# mixer_board_smd_full.net
KiCad netlist of a schematic drawn in EAGLE
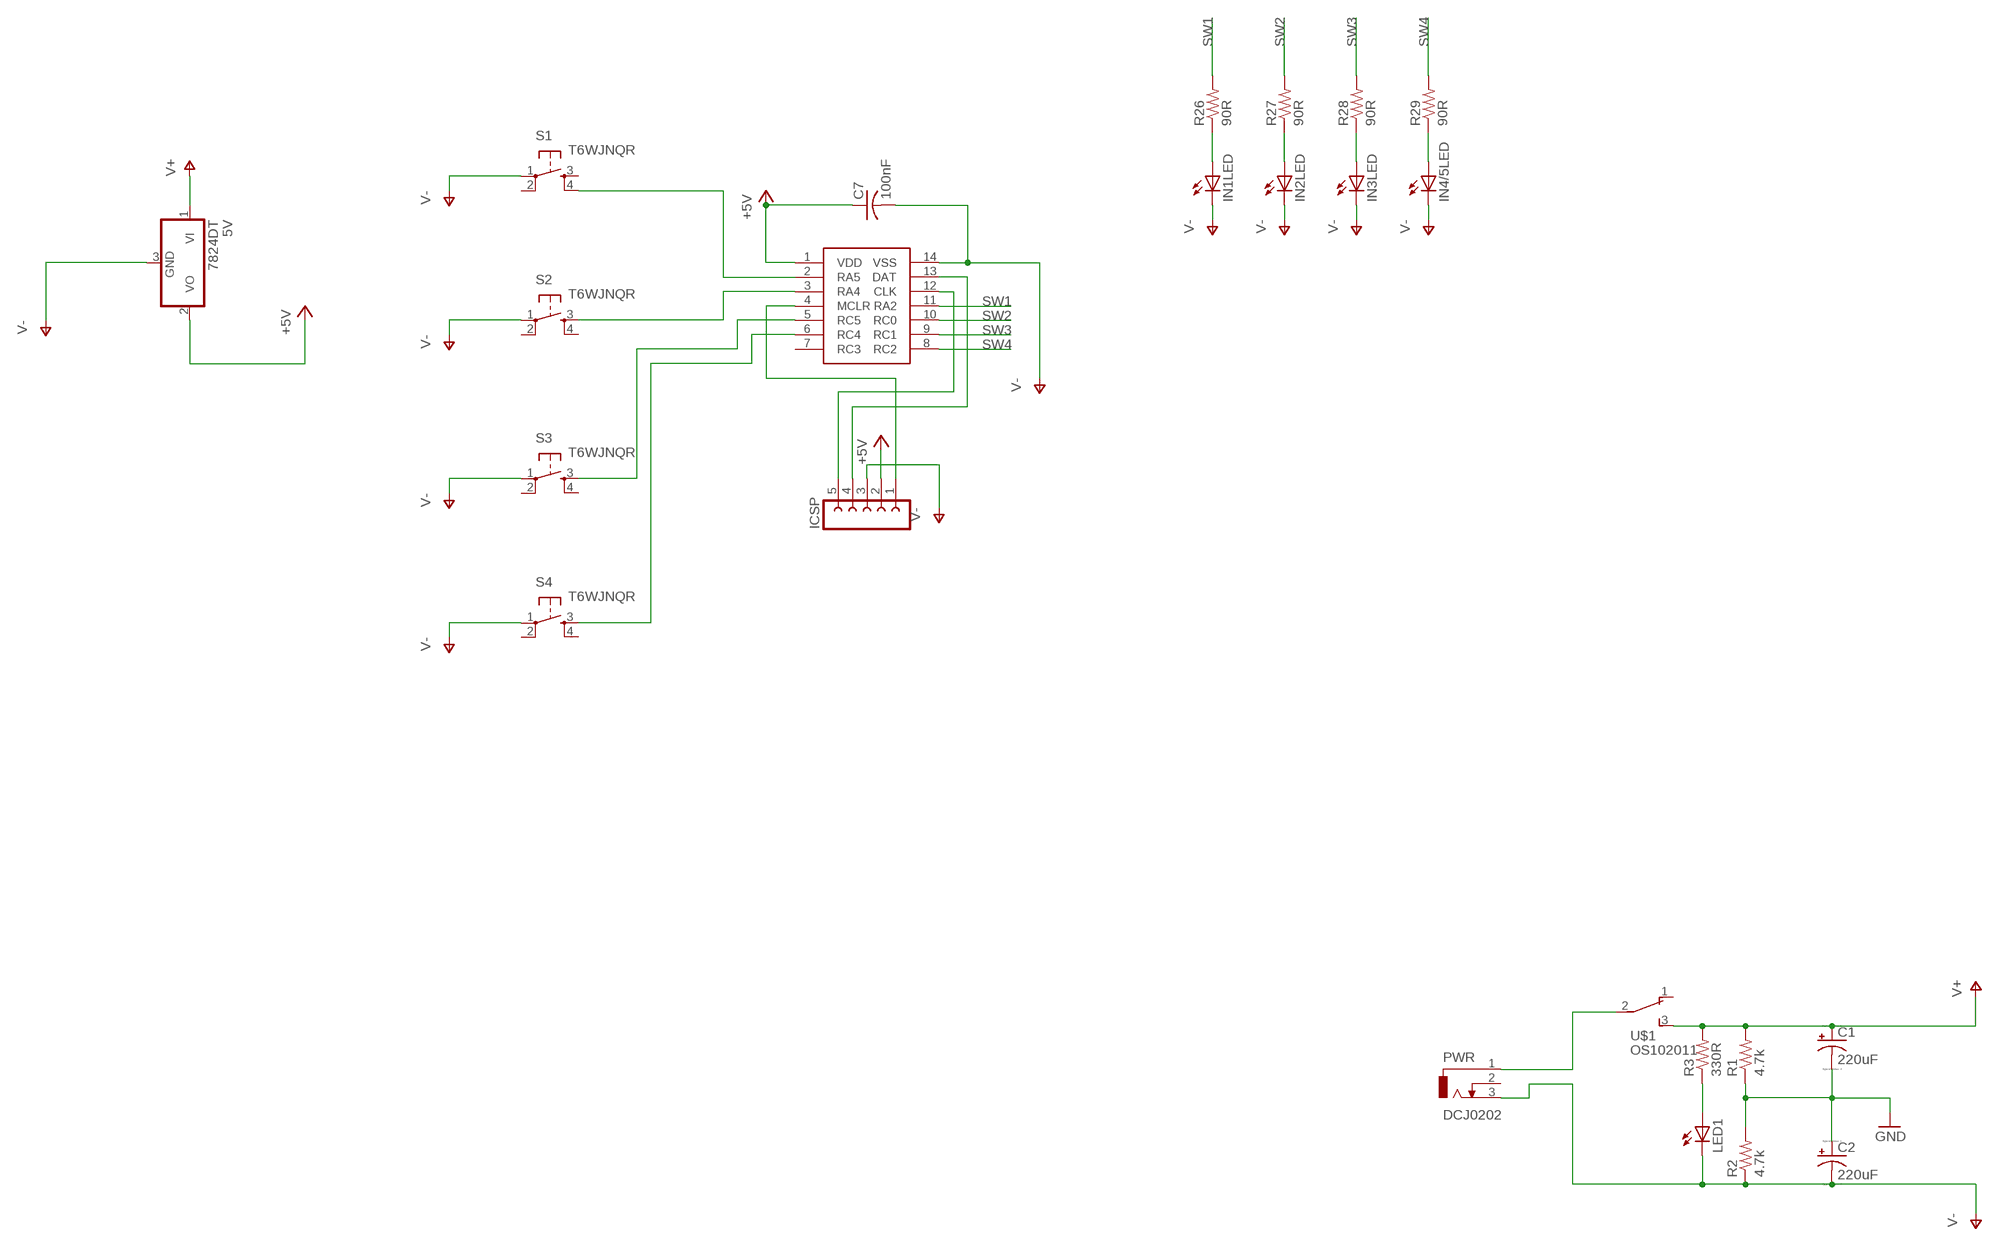
[diagram p0: schematic, sheet 1, part 1 of 2]
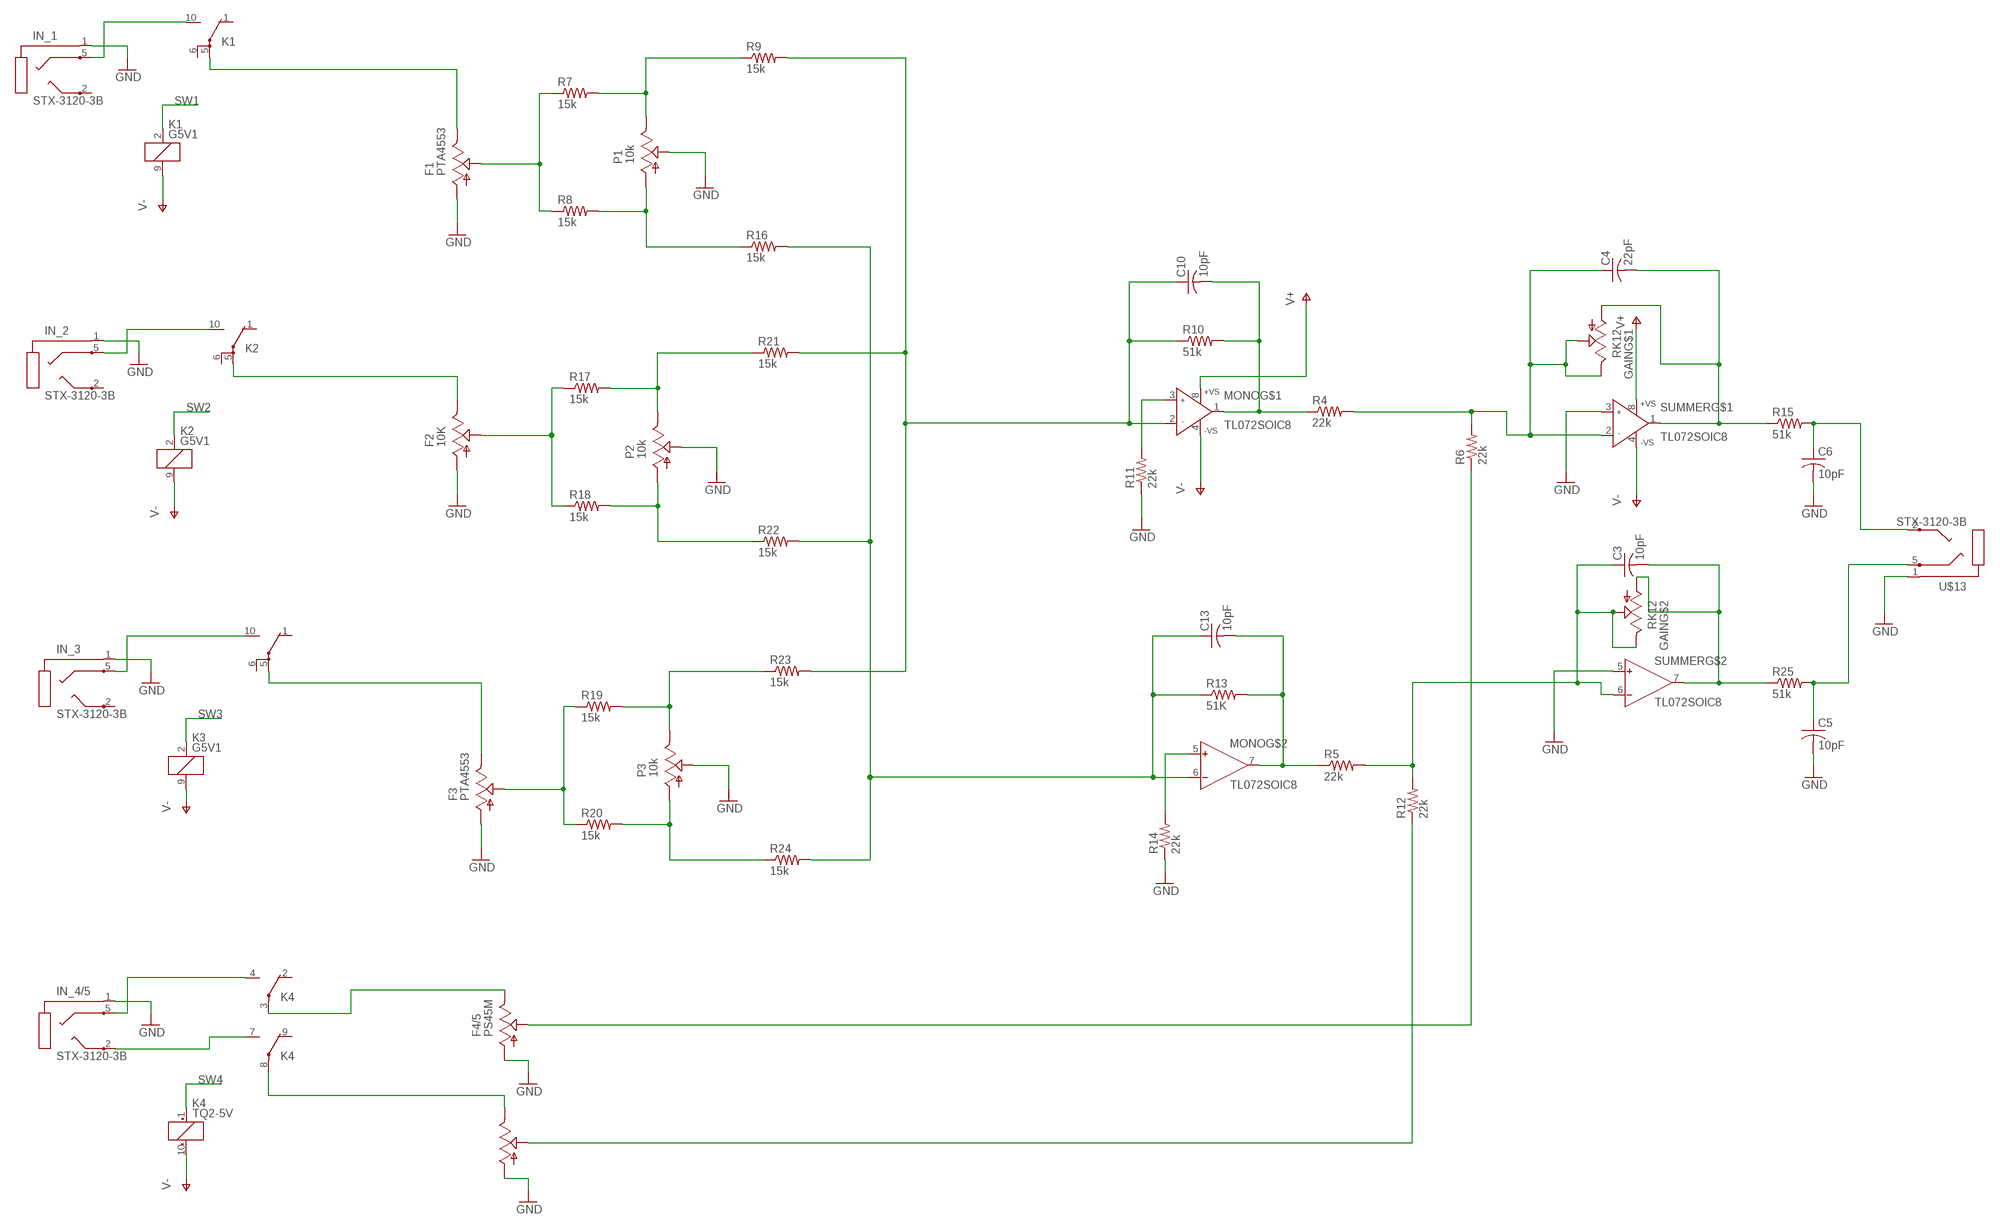
[diagram p1: schematic, sheet 1, part 2 of 2]

(export (version "E")
  (design (tool "Eeschema 10.0.6"))
  (components
    (comp (ref "5V")
      (value "7824DT")
      (footprint "eagle-import:TO252")
      (libsource (lib "eagle-import") (part "78DT24"))
    )
    (comp (ref "C1")
      (value "220uF")
      (footprint "eagle-import:E1,8-4")
      (libsource (lib "eagle-import") (part "CPOL-USE1.8-4"))
    )
    (comp (ref "C2")
      (value "220uF")
      (footprint "eagle-import:E1,8-4")
      (libsource (lib "eagle-import") (part "CPOL-USE1.8-4"))
    )
    (comp (ref "C3")
      (value "10pF")
      (footprint "eagle-import:C0805")
      (libsource (lib "eagle-import") (part "C-USC0805"))
    )
    (comp (ref "C4")
      (value "22pF")
      (footprint "eagle-import:C0805")
      (libsource (lib "eagle-import") (part "C-USC0805"))
    )
    (comp (ref "C5")
      (value "10pF")
      (footprint "eagle-import:C0805")
      (libsource (lib "eagle-import") (part "C-USC0805"))
    )
    (comp (ref "C6")
      (value "10pF")
      (footprint "eagle-import:C0805")
      (libsource (lib "eagle-import") (part "C-USC0805"))
    )
    (comp (ref "C7")
      (value "100nF")
      (footprint "eagle-import:C0805")
      (libsource (lib "eagle-import") (part "C-USC0805"))
    )
    (comp (ref "C10")
      (value "10pF")
      (footprint "eagle-import:C0805")
      (libsource (lib "eagle-import") (part "C-USC0805"))
    )
    (comp (ref "C13")
      (value "10pF")
      (footprint "eagle-import:C0805")
      (libsource (lib "eagle-import") (part "C-USC0805"))
    )
    (comp (ref "F1")
      (value "PTA4553")
      (footprint "eagle-import:PTA4553")
      (libsource (lib "eagle-import") (part "PTA4553"))
    )
    (comp (ref "F2")
      (value "10K")
      (footprint "eagle-import:PTA4553")
      (libsource (lib "eagle-import") (part "PTA4553"))
    )
    (comp (ref "F3")
      (value "PTA4553")
      (footprint "eagle-import:PTA4553")
      (libsource (lib "eagle-import") (part "PTA4553"))
    )
    (comp (ref "F4/5")
      (value "PS45M")
      (footprint "eagle-import:PS45M")
      (libsource (lib "eagle-import") (part "PS45M"))
    )
    (comp (ref "GAIN")
      (value "RK12")
      (footprint "eagle-import:RK12")
      (libsource (lib "eagle-import") (part "RK12"))
    )
    (comp (ref "ICSP")
      (value "FE05-1")
      (footprint "eagle-import:FE05-1")
      (libsource (lib "eagle-import") (part "FE05-1"))
    )
    (comp (ref "IN1LED")
      (value "LEDCHIPLED_1206")
      (footprint "eagle-import:CHIPLED_1206")
      (libsource (lib "eagle-import") (part "LEDCHIPLED_1206"))
    )
    (comp (ref "IN2LED")
      (value "LEDCHIPLED_1206")
      (footprint "eagle-import:CHIPLED_1206")
      (libsource (lib "eagle-import") (part "LEDCHIPLED_1206"))
    )
    (comp (ref "IN3LED")
      (value "LEDCHIPLED_1206")
      (footprint "eagle-import:CHIPLED_1206")
      (libsource (lib "eagle-import") (part "LEDCHIPLED_1206"))
    )
    (comp (ref "IN4/5LED")
      (value "LEDCHIPLED_1206")
      (footprint "eagle-import:CHIPLED_1206")
      (libsource (lib "eagle-import") (part "LEDCHIPLED_1206"))
    )
    (comp (ref "IN_1")
      (value "STX-3120-3B")
      (footprint "eagle-import:STX-3120")
      (libsource (lib "eagle-import") (part "STX-3120-3B"))
    )
    (comp (ref "IN_2")
      (value "STX-3120-3B")
      (footprint "eagle-import:STX-3120")
      (libsource (lib "eagle-import") (part "STX-3120-3B"))
    )
    (comp (ref "IN_3")
      (value "STX-3120-3B")
      (footprint "eagle-import:STX-3120")
      (libsource (lib "eagle-import") (part "STX-3120-3B"))
    )
    (comp (ref "IN_4/5")
      (value "STX-3120-3B")
      (footprint "eagle-import:STX-3120")
      (libsource (lib "eagle-import") (part "STX-3120-3B"))
    )
    (comp (ref "K1")
      (value "G5V1")
      (footprint "eagle-import:G5V1")
      (fields (field (name "MPN") "G5V-1-DC24"))
      (libsource (lib "eagle-import") (part "G5V1"))
    )
    (comp (ref "K2")
      (value "G5V1")
      (footprint "eagle-import:G5V1")
      (fields (field (name "MPN") "G5V-1-DC24"))
      (libsource (lib "eagle-import") (part "G5V1"))
    )
    (comp (ref "K3")
      (value "G5V1")
      (footprint "eagle-import:G5V1")
      (fields (field (name "MPN") "G5V-1-DC24"))
      (libsource (lib "eagle-import") (part "G5V1"))
    )
    (comp (ref "K4")
      (value "TQ2-5V")
      (footprint "eagle-import:TQ2")
      (fields (field (name "MF") "AROMAT/ MATSUSHITA"))
      (libsource (lib "eagle-import") (part "TQ2?-5V"))
    )
    (comp (ref "LED1")
      (value "LEDCHIPLED_1206")
      (footprint "eagle-import:CHIPLED_1206")
      (libsource (lib "eagle-import") (part "LEDCHIPLED_1206"))
    )
    (comp (ref "MONO")
      (value "TL072SOIC8")
      (footprint "eagle-import:SOIC8")
      (libsource (lib "eagle-import") (part "TL072SOIC8"))
    )
    (comp (ref "P1")
      (value "10k")
      (footprint "eagle-import:PTV09A")
      (libsource (lib "eagle-import") (part "PTV09A"))
    )
    (comp (ref "P2")
      (value "10k")
      (footprint "eagle-import:PTV09A")
      (libsource (lib "eagle-import") (part "PTV09A"))
    )
    (comp (ref "P3")
      (value "10k")
      (footprint "eagle-import:PTV09A")
      (libsource (lib "eagle-import") (part "PTV09A"))
    )
    (comp (ref "PIC16")
      (value "PIC16F18426")
      (footprint "eagle-import:SO14")
      (libsource (lib "eagle-import") (part "PIC16F18426"))
    )
    (comp (ref "PWR")
      (value "DCJ0202")
      (footprint "eagle-import:DCJ0202")
      (libsource (lib "eagle-import") (part "DCJ0202"))
    )
    (comp (ref "R1")
      (value "4.7k")
      (footprint "eagle-import:M0805")
      (libsource (lib "eagle-import") (part "R-US_M0805"))
    )
    (comp (ref "R2")
      (value "4.7k")
      (footprint "eagle-import:M0805")
      (libsource (lib "eagle-import") (part "R-US_M0805"))
    )
    (comp (ref "R3")
      (value "330R")
      (footprint "eagle-import:R0805")
      (libsource (lib "eagle-import") (part "R-US_R0805"))
    )
    (comp (ref "R4")
      (value "22k")
      (footprint "eagle-import:M0805")
      (libsource (lib "eagle-import") (part "R-US_M0805"))
    )
    (comp (ref "R5")
      (value "22k")
      (footprint "eagle-import:M0805")
      (libsource (lib "eagle-import") (part "R-US_M0805"))
    )
    (comp (ref "R6")
      (value "22k")
      (footprint "eagle-import:M0805")
      (libsource (lib "eagle-import") (part "R-US_M0805"))
    )
    (comp (ref "R7")
      (value "15k")
      (footprint "eagle-import:M0805")
      (libsource (lib "eagle-import") (part "R-US_M0805"))
    )
    (comp (ref "R8")
      (value "15k")
      (footprint "eagle-import:M0805")
      (libsource (lib "eagle-import") (part "R-US_M0805"))
    )
    (comp (ref "R9")
      (value "15k")
      (footprint "eagle-import:M0805")
      (libsource (lib "eagle-import") (part "R-US_M0805"))
    )
    (comp (ref "R10")
      (value "51k")
      (footprint "eagle-import:M0805")
      (libsource (lib "eagle-import") (part "R-US_M0805"))
    )
    (comp (ref "R11")
      (value "22k")
      (footprint "eagle-import:M0805")
      (libsource (lib "eagle-import") (part "R-US_M0805"))
    )
    (comp (ref "R12")
      (value "22k")
      (footprint "eagle-import:M0805")
      (libsource (lib "eagle-import") (part "R-US_M0805"))
    )
    (comp (ref "R13")
      (value "51K")
      (footprint "eagle-import:M0805")
      (libsource (lib "eagle-import") (part "R-US_M0805"))
    )
    (comp (ref "R14")
      (value "22k")
      (footprint "eagle-import:M0805")
      (libsource (lib "eagle-import") (part "R-US_M0805"))
    )
    (comp (ref "R15")
      (value "51k")
      (footprint "eagle-import:M0805")
      (libsource (lib "eagle-import") (part "R-US_M0805"))
    )
    (comp (ref "R16")
      (value "15k")
      (footprint "eagle-import:M0805")
      (libsource (lib "eagle-import") (part "R-US_M0805"))
    )
    (comp (ref "R17")
      (value "15k")
      (footprint "eagle-import:M0805")
      (libsource (lib "eagle-import") (part "R-US_M0805"))
    )
    (comp (ref "R18")
      (value "15k")
      (footprint "eagle-import:M0805")
      (libsource (lib "eagle-import") (part "R-US_M0805"))
    )
    (comp (ref "R19")
      (value "15k")
      (footprint "eagle-import:M0805")
      (libsource (lib "eagle-import") (part "R-US_M0805"))
    )
    (comp (ref "R20")
      (value "15k")
      (footprint "eagle-import:M0805")
      (libsource (lib "eagle-import") (part "R-US_M0805"))
    )
    (comp (ref "R21")
      (value "15k")
      (footprint "eagle-import:M0805")
      (libsource (lib "eagle-import") (part "R-US_M0805"))
    )
    (comp (ref "R22")
      (value "15k")
      (footprint "eagle-import:M0805")
      (libsource (lib "eagle-import") (part "R-US_M0805"))
    )
    (comp (ref "R23")
      (value "15k")
      (footprint "eagle-import:M0805")
      (libsource (lib "eagle-import") (part "R-US_M0805"))
    )
    (comp (ref "R24")
      (value "15k")
      (footprint "eagle-import:M0805")
      (libsource (lib "eagle-import") (part "R-US_M0805"))
    )
    (comp (ref "R25")
      (value "51k")
      (footprint "eagle-import:M0805")
      (libsource (lib "eagle-import") (part "R-US_M0805"))
    )
    (comp (ref "R26")
      (value "90R")
      (footprint "eagle-import:M0805")
      (libsource (lib "eagle-import") (part "R-US_M0805"))
    )
    (comp (ref "R27")
      (value "90R")
      (footprint "eagle-import:M0805")
      (libsource (lib "eagle-import") (part "R-US_M0805"))
    )
    (comp (ref "R28")
      (value "90R")
      (footprint "eagle-import:M0805")
      (libsource (lib "eagle-import") (part "R-US_M0805"))
    )
    (comp (ref "R29")
      (value "90R")
      (footprint "eagle-import:M0805")
      (libsource (lib "eagle-import") (part "R-US_M0805"))
    )
    (comp (ref "S1")
      (value "T6WJNQR")
      (footprint "eagle-import:T6WJ2NGQR")
      (libsource (lib "eagle-import") (part "T6WJNQR"))
    )
    (comp (ref "S2")
      (value "T6WJNQR")
      (footprint "eagle-import:T6WJ2NGQR")
      (libsource (lib "eagle-import") (part "T6WJNQR"))
    )
    (comp (ref "S3")
      (value "T6WJNQR")
      (footprint "eagle-import:T6WJ2NGQR")
      (libsource (lib "eagle-import") (part "T6WJNQR"))
    )
    (comp (ref "S4")
      (value "T6WJNQR")
      (footprint "eagle-import:T6WJ2NGQR")
      (libsource (lib "eagle-import") (part "T6WJNQR"))
    )
    (comp (ref "SUMMER")
      (value "TL072SOIC8")
      (footprint "eagle-import:SOIC8")
      (libsource (lib "eagle-import") (part "TL072SOIC8"))
    )
    (comp (ref "U$1")
      (value "OS102011")
      (footprint "eagle-import:OS102011")
      (libsource (lib "eagle-import") (part "OS102011"))
    )
    (comp (ref "U$13")
      (value "STX-3120-3B")
      (footprint "eagle-import:STX-3120")
      (libsource (lib "eagle-import") (part "STX-3120-3B"))
    )
  )
  (nets
    (net (code "1") (name "+5V") (class "Default")
      (node (ref "5V") (pin "2") (pinfunction "VO_2") (pintype "passive"))
      (node (ref "C7") (pin "1") (pinfunction "1_1") (pintype "passive"))
      (node (ref "ICSP") (pin "2") (pinfunction "2_2") (pintype "passive"))
      (node (ref "PIC16") (pin "1") (pinfunction "VDD_1") (pintype "bidirectional"))
    )
    (net (code "2") (name "/SW1") (class "Default")
      (node (ref "K1") (pin "2") (pinfunction "1_2") (pintype "passive"))
      (node (ref "PIC16") (pin "11") (pinfunction "RA2_11") (pintype "bidirectional"))
      (node (ref "R26") (pin "2") (pinfunction "2_2") (pintype "passive"))
    )
    (net (code "3") (name "/SW2") (class "Default")
      (node (ref "K2") (pin "2") (pinfunction "1_2") (pintype "passive"))
      (node (ref "PIC16") (pin "10") (pinfunction "RC0_10") (pintype "bidirectional"))
      (node (ref "R27") (pin "2") (pinfunction "2_2") (pintype "passive"))
    )
    (net (code "4") (name "/SW3") (class "Default")
      (node (ref "K3") (pin "2") (pinfunction "1_2") (pintype "passive"))
      (node (ref "PIC16") (pin "9") (pinfunction "RC1_9") (pintype "bidirectional"))
      (node (ref "R28") (pin "2") (pinfunction "2_2") (pintype "passive"))
    )
    (net (code "5") (name "/SW4") (class "Default")
      (node (ref "K4") (pin "1") (pinfunction "+_1") (pintype "passive"))
      (node (ref "PIC16") (pin "8") (pinfunction "RC2_8") (pintype "bidirectional"))
      (node (ref "R29") (pin "2") (pinfunction "2_2") (pintype "passive"))
    )
    (net (code "6") (name "GND") (class "Default")
      (node (ref "C1") (pin "-") (pinfunction "-_-") (pintype "passive"))
      (node (ref "C2") (pin "+") (pinfunction "+_+") (pintype "passive"))
      (node (ref "C5") (pin "2") (pinfunction "2_2") (pintype "passive"))
      (node (ref "C6") (pin "2") (pinfunction "2_2") (pintype "passive"))
      (node (ref "F1") (pin "1") (pinfunction "1_1") (pintype "passive"))
      (node (ref "F2") (pin "1") (pinfunction "1_1") (pintype "passive"))
      (node (ref "F3") (pin "1") (pinfunction "1_1") (pintype "passive"))
      (node (ref "F4/5") (pin "1") (pinfunction "1_1") (pintype "passive"))
      (node (ref "F4/5") (pin "1'") (pinfunction "1'_1'") (pintype "passive"))
      (node (ref "IN_1") (pin "1") (pinfunction "1_1") (pintype "passive"))
      (node (ref "IN_2") (pin "1") (pinfunction "1_1") (pintype "passive"))
      (node (ref "IN_3") (pin "1") (pinfunction "1_1") (pintype "passive"))
      (node (ref "IN_4/5") (pin "1") (pinfunction "1_1") (pintype "passive"))
      (node (ref "P1") (pin "2") (pinfunction "2_2") (pintype "passive"))
      (node (ref "P2") (pin "2") (pinfunction "2_2") (pintype "passive"))
      (node (ref "P3") (pin "2") (pinfunction "2_2") (pintype "passive"))
      (node (ref "R1") (pin "1") (pinfunction "1_1") (pintype "passive"))
      (node (ref "R11") (pin "1") (pinfunction "1_1") (pintype "passive"))
      (node (ref "R14") (pin "1") (pinfunction "1_1") (pintype "passive"))
      (node (ref "R2") (pin "2") (pinfunction "2_2") (pintype "passive"))
      (node (ref "SUMMER") (pin "3") (pinfunction "IN+_3") (pintype "input"))
      (node (ref "SUMMER") (pin "5") (pinfunction "IN+_5") (pintype "input"))
      (node (ref "U$13") (pin "1") (pinfunction "1_1") (pintype "passive"))
    )
    (net (code "7") (name "Net-(C5-Pad1)") (class "Default")
      (node (ref "C5") (pin "1") (pinfunction "1_1") (pintype "passive"))
      (node (ref "R25") (pin "2") (pinfunction "2_2") (pintype "passive"))
      (node (ref "U$13") (pin "5") (pinfunction "5_5") (pintype "passive"))
    )
    (net (code "8") (name "Net-(C6-Pad1)") (class "Default")
      (node (ref "C6") (pin "1") (pinfunction "1_1") (pintype "passive"))
      (node (ref "R15") (pin "2") (pinfunction "2_2") (pintype "passive"))
      (node (ref "U$13") (pin "2") (pinfunction "2_2") (pintype "passive"))
    )
    (net (code "9") (name "Net-(F1-Pad2)") (class "Default")
      (node (ref "F1") (pin "2") (pinfunction "2_2") (pintype "passive"))
      (node (ref "R7") (pin "1") (pinfunction "1_1") (pintype "passive"))
      (node (ref "R8") (pin "1") (pinfunction "1_1") (pintype "passive"))
    )
    (net (code "10") (name "Net-(F1-Pad3)") (class "Default")
      (node (ref "F1") (pin "3") (pinfunction "3_3") (pintype "passive"))
      (node (ref "K1") (pin "5") (pinfunction "P_5") (pintype "passive"))
    )
    (net (code "11") (name "Net-(F2-Pad2)") (class "Default")
      (node (ref "F2") (pin "2") (pinfunction "2_2") (pintype "passive"))
      (node (ref "R17") (pin "1") (pinfunction "1_1") (pintype "passive"))
      (node (ref "R18") (pin "1") (pinfunction "1_1") (pintype "passive"))
    )
    (net (code "12") (name "Net-(F2-Pad3)") (class "Default")
      (node (ref "F2") (pin "3") (pinfunction "3_3") (pintype "passive"))
      (node (ref "K2") (pin "5") (pinfunction "P_5") (pintype "passive"))
    )
    (net (code "13") (name "Net-(F3-Pad2)") (class "Default")
      (node (ref "F3") (pin "2") (pinfunction "2_2") (pintype "passive"))
      (node (ref "R19") (pin "1") (pinfunction "1_1") (pintype "passive"))
      (node (ref "R20") (pin "1") (pinfunction "1_1") (pintype "passive"))
    )
    (net (code "14") (name "Net-(F3-Pad3)") (class "Default")
      (node (ref "F3") (pin "3") (pinfunction "3_3") (pintype "passive"))
      (node (ref "K3") (pin "5") (pinfunction "P_5") (pintype "passive"))
    )
    (net (code "15") (name "Net-(F4/5-Pad2')") (class "Default")
      (node (ref "F4/5") (pin "2'") (pinfunction "2'_2'") (pintype "passive"))
      (node (ref "R12") (pin "1") (pinfunction "1_1") (pintype "passive"))
    )
    (net (code "16") (name "Net-(F4/5-Pad2)") (class "Default")
      (node (ref "F4/5") (pin "2") (pinfunction "2_2") (pintype "passive"))
      (node (ref "R6") (pin "1") (pinfunction "1_1") (pintype "passive"))
    )
    (net (code "17") (name "Net-(GAINB-1)") (class "Default")
      (node (ref "C3") (pin "2") (pinfunction "2_2") (pintype "passive"))
      (node (ref "GAIN") (pin "1'") (pinfunction "1_1'") (pintype "passive"))
      (node (ref "R25") (pin "1") (pinfunction "1_1") (pintype "passive"))
      (node (ref "SUMMER") (pin "7") (pinfunction "OUT_7") (pintype "output"))
    )
    (net (code "18") (name "Net-(GAINB-2)") (class "Default")
      (node (ref "C3") (pin "1") (pinfunction "1_1") (pintype "passive"))
      (node (ref "GAIN") (pin "2'") (pinfunction "2_2'") (pintype "passive"))
      (node (ref "GAIN") (pin "3'") (pinfunction "3_3'") (pintype "passive"))
      (node (ref "R12") (pin "2") (pinfunction "2_2") (pintype "passive"))
      (node (ref "R5") (pin "2") (pinfunction "2_2") (pintype "passive"))
      (node (ref "SUMMER") (pin "6") (pinfunction "IN-_6") (pintype "input"))
    )
    (net (code "19") (name "Net-(IN1LED-PadA)") (class "Default")
      (node (ref "IN1LED") (pin "A") (pinfunction "A_A") (pintype "passive"))
      (node (ref "R26") (pin "1") (pinfunction "1_1") (pintype "passive"))
    )
    (net (code "20") (name "Net-(IN2LED-PadA)") (class "Default")
      (node (ref "IN2LED") (pin "A") (pinfunction "A_A") (pintype "passive"))
      (node (ref "R27") (pin "1") (pinfunction "1_1") (pintype "passive"))
    )
    (net (code "21") (name "Net-(IN3LED-PadA)") (class "Default")
      (node (ref "IN3LED") (pin "A") (pinfunction "A_A") (pintype "passive"))
      (node (ref "R28") (pin "1") (pinfunction "1_1") (pintype "passive"))
    )
    (net (code "22") (name "Net-(IN4/5LED-PadA)") (class "Default")
      (node (ref "IN4/5LED") (pin "A") (pinfunction "A_A") (pintype "passive"))
      (node (ref "R29") (pin "1") (pinfunction "1_1") (pintype "passive"))
    )
    (net (code "23") (name "Net-(K1B-S)") (class "Default")
      (node (ref "IN_1") (pin "5") (pinfunction "5_5") (pintype "passive"))
      (node (ref "K1") (pin "10") (pinfunction "S_10") (pintype "passive"))
    )
    (net (code "24") (name "Net-(K2B-S)") (class "Default")
      (node (ref "IN_2") (pin "5") (pinfunction "5_5") (pintype "passive"))
      (node (ref "K2") (pin "10") (pinfunction "S_10") (pintype "passive"))
    )
    (net (code "25") (name "Net-(K3B-S)") (class "Default")
      (node (ref "IN_3") (pin "5") (pinfunction "5_5") (pintype "passive"))
      (node (ref "K3") (pin "10") (pinfunction "S_10") (pintype "passive"))
    )
    (net (code "26") (name "Net-(K4A-P)") (class "Default")
      (node (ref "F4/5") (pin "3") (pinfunction "3_3") (pintype "passive"))
      (node (ref "K4") (pin "3") (pinfunction "P_3") (pintype "passive"))
    )
    (net (code "27") (name "Net-(K4A-S)") (class "Default")
      (node (ref "IN_4/5") (pin "5") (pinfunction "5_5") (pintype "passive"))
      (node (ref "K4") (pin "4") (pinfunction "S_4") (pintype "passive"))
    )
    (net (code "28") (name "Net-(K4B-P)") (class "Default")
      (node (ref "F4/5") (pin "3'") (pinfunction "3'_3'") (pintype "passive"))
      (node (ref "K4") (pin "8") (pinfunction "P_8") (pintype "passive"))
    )
    (net (code "29") (name "Net-(K4B-S)") (class "Default")
      (node (ref "IN_4/5") (pin "2") (pinfunction "2_2") (pintype "passive"))
      (node (ref "K4") (pin "7") (pinfunction "S_7") (pintype "passive"))
    )
    (net (code "30") (name "Net-(LED1-PadA)") (class "Default")
      (node (ref "LED1") (pin "A") (pinfunction "A_A") (pintype "passive"))
      (node (ref "R3") (pin "1") (pinfunction "1_1") (pintype "passive"))
    )
    (net (code "31") (name "Net-(MONOA-IN+)") (class "Default")
      (node (ref "MONO") (pin "3") (pinfunction "IN+_3") (pintype "input"))
      (node (ref "R11") (pin "2") (pinfunction "2_2") (pintype "passive"))
    )
    (net (code "32") (name "Net-(MONOA-IN-)") (class "Default")
      (node (ref "C10") (pin "1") (pinfunction "1_1") (pintype "passive"))
      (node (ref "MONO") (pin "2") (pinfunction "IN-_2") (pintype "input"))
      (node (ref "R10") (pin "1") (pinfunction "1_1") (pintype "passive"))
      (node (ref "R21") (pin "2") (pinfunction "2_2") (pintype "passive"))
      (node (ref "R23") (pin "2") (pinfunction "2_2") (pintype "passive"))
      (node (ref "R9") (pin "2") (pinfunction "2_2") (pintype "passive"))
    )
    (net (code "33") (name "Net-(MONOA-OUT)") (class "Default")
      (node (ref "C10") (pin "2") (pinfunction "2_2") (pintype "passive"))
      (node (ref "MONO") (pin "1") (pinfunction "OUT_1") (pintype "output"))
      (node (ref "R10") (pin "2") (pinfunction "2_2") (pintype "passive"))
      (node (ref "R4") (pin "1") (pinfunction "1_1") (pintype "passive"))
    )
    (net (code "34") (name "Net-(MONOB-IN+)") (class "Default")
      (node (ref "MONO") (pin "5") (pinfunction "IN+_5") (pintype "input"))
      (node (ref "R14") (pin "2") (pinfunction "2_2") (pintype "passive"))
    )
    (net (code "35") (name "Net-(MONOB-IN-)") (class "Default")
      (node (ref "C13") (pin "1") (pinfunction "1_1") (pintype "passive"))
      (node (ref "MONO") (pin "6") (pinfunction "IN-_6") (pintype "input"))
      (node (ref "R13") (pin "1") (pinfunction "1_1") (pintype "passive"))
      (node (ref "R16") (pin "2") (pinfunction "2_2") (pintype "passive"))
      (node (ref "R22") (pin "2") (pinfunction "2_2") (pintype "passive"))
      (node (ref "R24") (pin "2") (pinfunction "2_2") (pintype "passive"))
    )
    (net (code "36") (name "Net-(MONOB-OUT)") (class "Default")
      (node (ref "C13") (pin "2") (pinfunction "2_2") (pintype "passive"))
      (node (ref "MONO") (pin "7") (pinfunction "OUT_7") (pintype "output"))
      (node (ref "R13") (pin "2") (pinfunction "2_2") (pintype "passive"))
      (node (ref "R5") (pin "1") (pinfunction "1_1") (pintype "passive"))
    )
    (net (code "37") (name "Net-(P1-Pad1)") (class "Default")
      (node (ref "P1") (pin "1") (pinfunction "1_1") (pintype "passive"))
      (node (ref "R16") (pin "1") (pinfunction "1_1") (pintype "passive"))
      (node (ref "R8") (pin "2") (pinfunction "2_2") (pintype "passive"))
    )
    (net (code "38") (name "Net-(P1-Pad3)") (class "Default")
      (node (ref "P1") (pin "3") (pinfunction "3_3") (pintype "passive"))
      (node (ref "R7") (pin "2") (pinfunction "2_2") (pintype "passive"))
      (node (ref "R9") (pin "1") (pinfunction "1_1") (pintype "passive"))
    )
    (net (code "39") (name "Net-(P2-Pad1)") (class "Default")
      (node (ref "P2") (pin "1") (pinfunction "1_1") (pintype "passive"))
      (node (ref "R18") (pin "2") (pinfunction "2_2") (pintype "passive"))
      (node (ref "R22") (pin "1") (pinfunction "1_1") (pintype "passive"))
    )
    (net (code "40") (name "Net-(P2-Pad3)") (class "Default")
      (node (ref "P2") (pin "3") (pinfunction "3_3") (pintype "passive"))
      (node (ref "R17") (pin "2") (pinfunction "2_2") (pintype "passive"))
      (node (ref "R21") (pin "1") (pinfunction "1_1") (pintype "passive"))
    )
    (net (code "41") (name "Net-(P3-Pad1)") (class "Default")
      (node (ref "P3") (pin "1") (pinfunction "1_1") (pintype "passive"))
      (node (ref "R20") (pin "2") (pinfunction "2_2") (pintype "passive"))
      (node (ref "R24") (pin "1") (pinfunction "1_1") (pintype "passive"))
    )
    (net (code "42") (name "Net-(P3-Pad3)") (class "Default")
      (node (ref "P3") (pin "3") (pinfunction "3_3") (pintype "passive"))
      (node (ref "R19") (pin "2") (pinfunction "2_2") (pintype "passive"))
      (node (ref "R23") (pin "1") (pinfunction "1_1") (pintype "passive"))
    )
    (net (code "43") (name "Net-(PIC16-CLK)") (class "Default")
      (node (ref "ICSP") (pin "5") (pinfunction "5_5") (pintype "passive"))
      (node (ref "PIC16") (pin "12") (pinfunction "CLK_12") (pintype "bidirectional"))
    )
    (net (code "44") (name "Net-(PIC16-DAT)") (class "Default")
      (node (ref "ICSP") (pin "4") (pinfunction "4_4") (pintype "passive"))
      (node (ref "PIC16") (pin "13") (pinfunction "DAT_13") (pintype "bidirectional"))
    )
    (net (code "45") (name "Net-(PIC16-MCLR)") (class "Default")
      (node (ref "ICSP") (pin "1") (pinfunction "1_1") (pintype "passive"))
      (node (ref "PIC16") (pin "4") (pinfunction "MCLR_4") (pintype "bidirectional"))
    )
    (net (code "46") (name "Net-(PIC16-RA4)") (class "Default")
      (node (ref "PIC16") (pin "3") (pinfunction "RA4_3") (pintype "bidirectional"))
      (node (ref "S2") (pin "3") (pinfunction "3_3") (pintype "passive"))
    )
    (net (code "47") (name "Net-(PIC16-RA5)") (class "Default")
      (node (ref "PIC16") (pin "2") (pinfunction "RA5_2") (pintype "bidirectional"))
      (node (ref "S1") (pin "4") (pinfunction "4_4") (pintype "passive"))
    )
    (net (code "48") (name "Net-(PIC16-RC4)") (class "Default")
      (node (ref "PIC16") (pin "6") (pinfunction "RC4_6") (pintype "bidirectional"))
      (node (ref "S4") (pin "3") (pinfunction "3_3") (pintype "passive"))
    )
    (net (code "49") (name "Net-(PIC16-RC5)") (class "Default")
      (node (ref "PIC16") (pin "5") (pinfunction "RC5_5") (pintype "bidirectional"))
      (node (ref "S3") (pin "3") (pinfunction "3_3") (pintype "passive"))
    )
    (net (code "50") (name "Net-(SUMMERA-IN-)") (class "Default")
      (node (ref "C4") (pin "1") (pinfunction "1_1") (pintype "passive"))
      (node (ref "GAIN") (pin "2") (pinfunction "2_2") (pintype "passive"))
      (node (ref "GAIN") (pin "3") (pinfunction "3_3") (pintype "passive"))
      (node (ref "R4") (pin "2") (pinfunction "2_2") (pintype "passive"))
      (node (ref "R6") (pin "2") (pinfunction "2_2") (pintype "passive"))
      (node (ref "SUMMER") (pin "2") (pinfunction "IN-_2") (pintype "input"))
    )
    (net (code "51") (name "Net-(SUMMERA-OUT)") (class "Default")
      (node (ref "C4") (pin "2") (pinfunction "2_2") (pintype "passive"))
      (node (ref "GAIN") (pin "1") (pinfunction "1_1") (pintype "passive"))
      (node (ref "R15") (pin "1") (pinfunction "1_1") (pintype "passive"))
      (node (ref "SUMMER") (pin "1") (pinfunction "OUT_1") (pintype "output"))
    )
    (net (code "52") (name "Net-(U$1-P)") (class "Default")
      (node (ref "PWR") (pin "1") (pinfunction "1_1") (pintype "passive"))
      (node (ref "U$1") (pin "2") (pinfunction "P_2") (pintype "passive"))
    )
    (net (code "53") (name "V+") (class "Default")
      (node (ref "5V") (pin "1") (pinfunction "VI_1") (pintype "input"))
      (node (ref "C1") (pin "+") (pinfunction "+_+") (pintype "passive"))
      (node (ref "MONO") (pin "8") (pinfunction "+VS_8") (pintype "input"))
      (node (ref "R1") (pin "2") (pinfunction "2_2") (pintype "passive"))
      (node (ref "R3") (pin "2") (pinfunction "2_2") (pintype "passive"))
      (node (ref "SUMMER") (pin "8") (pinfunction "+VS_8") (pintype "input"))
      (node (ref "U$1") (pin "3") (pinfunction "S_3") (pintype "passive"))
    )
    (net (code "54") (name "V-") (class "Default")
      (node (ref "5V") (pin "3") (pinfunction "GND_3") (pintype "passive"))
      (node (ref "C2") (pin "-") (pinfunction "-_-") (pintype "passive"))
      (node (ref "C7") (pin "2") (pinfunction "2_2") (pintype "passive"))
      (node (ref "ICSP") (pin "3") (pinfunction "3_3") (pintype "passive"))
      (node (ref "IN1LED") (pin "C") (pinfunction "C_C") (pintype "passive"))
      (node (ref "IN2LED") (pin "C") (pinfunction "C_C") (pintype "passive"))
      (node (ref "IN3LED") (pin "C") (pinfunction "C_C") (pintype "passive"))
      (node (ref "IN4/5LED") (pin "C") (pinfunction "C_C") (pintype "passive"))
      (node (ref "K1") (pin "9") (pinfunction "2_9") (pintype "passive"))
      (node (ref "K2") (pin "9") (pinfunction "2_9") (pintype "passive"))
      (node (ref "K3") (pin "9") (pinfunction "2_9") (pintype "passive"))
      (node (ref "K4") (pin "10") (pinfunction "-_10") (pintype "passive"))
      (node (ref "LED1") (pin "C") (pinfunction "C_C") (pintype "passive"))
      (node (ref "MONO") (pin "4") (pinfunction "-VS_4") (pintype "input"))
      (node (ref "PIC16") (pin "14") (pinfunction "VSS_14") (pintype "bidirectional"))
      (node (ref "PWR") (pin "3") (pinfunction "3_3") (pintype "passive"))
      (node (ref "R2") (pin "1") (pinfunction "1_1") (pintype "passive"))
      (node (ref "S1") (pin "1") (pinfunction "1_1") (pintype "passive"))
      (node (ref "S2") (pin "1") (pinfunction "1_1") (pintype "passive"))
      (node (ref "S3") (pin "1") (pinfunction "1_1") (pintype "passive"))
      (node (ref "S4") (pin "1") (pinfunction "1_1") (pintype "passive"))
      (node (ref "SUMMER") (pin "4") (pinfunction "-VS_4") (pintype "input"))
    )
    (net (code "55") (name "unconnected-(IN_1-Pad2)") (class "Default")
      (node (ref "IN_1") (pin "2") (pinfunction "2_2") (pintype "passive"))
    )
    (net (code "56") (name "unconnected-(IN_2-Pad2)") (class "Default")
      (node (ref "IN_2") (pin "2") (pinfunction "2_2") (pintype "passive"))
    )
    (net (code "57") (name "unconnected-(IN_3-Pad2)") (class "Default")
      (node (ref "IN_3") (pin "2") (pinfunction "2_2") (pintype "passive"))
    )
    (net (code "58") (name "unconnected-(K1B-O-Pad1)") (class "Default")
      (node (ref "K1") (pin "1") (pinfunction "O_1") (pintype "passive"))
    )
    (net (code "59") (name "unconnected-(K1B-P-Pad6)") (class "Default")
      (node (ref "K1") (pin "6") (pinfunction "P_6") (pintype "passive"))
    )
    (net (code "60") (name "unconnected-(K2B-O-Pad1)") (class "Default")
      (node (ref "K2") (pin "1") (pinfunction "O_1") (pintype "passive"))
    )
    (net (code "61") (name "unconnected-(K2B-P-Pad6)") (class "Default")
      (node (ref "K2") (pin "6") (pinfunction "P_6") (pintype "passive"))
    )
    (net (code "62") (name "unconnected-(K3B-O-Pad1)") (class "Default")
      (node (ref "K3") (pin "1") (pinfunction "O_1") (pintype "passive"))
    )
    (net (code "63") (name "unconnected-(K3B-P-Pad6)") (class "Default")
      (node (ref "K3") (pin "6") (pinfunction "P_6") (pintype "passive"))
    )
    (net (code "64") (name "unconnected-(K4A-O-Pad2)") (class "Default")
      (node (ref "K4") (pin "2") (pinfunction "O_2") (pintype "passive"))
    )
    (net (code "65") (name "unconnected-(K4B-O-Pad9)") (class "Default")
      (node (ref "K4") (pin "9") (pinfunction "O_9") (pintype "passive"))
    )
    (net (code "66") (name "unconnected-(PIC16-RC3-Pad7)") (class "Default")
      (node (ref "PIC16") (pin "7") (pinfunction "RC3_7") (pintype "bidirectional"))
    )
    (net (code "67") (name "unconnected-(PWR-Pad2)") (class "Default")
      (node (ref "PWR") (pin "2") (pinfunction "2_2") (pintype "passive"))
    )
    (net (code "68") (name "unconnected-(S1-Pad2)") (class "Default")
      (node (ref "S1") (pin "2") (pinfunction "2_2") (pintype "passive"))
    )
    (net (code "69") (name "unconnected-(S1-Pad3)") (class "Default")
      (node (ref "S1") (pin "3") (pinfunction "3_3") (pintype "passive"))
    )
    (net (code "70") (name "unconnected-(S2-Pad2)") (class "Default")
      (node (ref "S2") (pin "2") (pinfunction "2_2") (pintype "passive"))
    )
    (net (code "71") (name "unconnected-(S2-Pad4)") (class "Default")
      (node (ref "S2") (pin "4") (pinfunction "4_4") (pintype "passive"))
    )
    (net (code "72") (name "unconnected-(S3-Pad2)") (class "Default")
      (node (ref "S3") (pin "2") (pinfunction "2_2") (pintype "passive"))
    )
    (net (code "73") (name "unconnected-(S3-Pad4)") (class "Default")
      (node (ref "S3") (pin "4") (pinfunction "4_4") (pintype "passive"))
    )
    (net (code "74") (name "unconnected-(S4-Pad2)") (class "Default")
      (node (ref "S4") (pin "2") (pinfunction "2_2") (pintype "passive"))
    )
    (net (code "75") (name "unconnected-(S4-Pad4)") (class "Default")
      (node (ref "S4") (pin "4") (pinfunction "4_4") (pintype "passive"))
    )
    (net (code "76") (name "unconnected-(U$1-O-Pad1)") (class "Default")
      (node (ref "U$1") (pin "1") (pinfunction "O_1") (pintype "passive"))
    )
  )
)
